# Z80_Card_for_Commodore_C64.net
KiCad netlist of a schematic drawn in Altium Designer
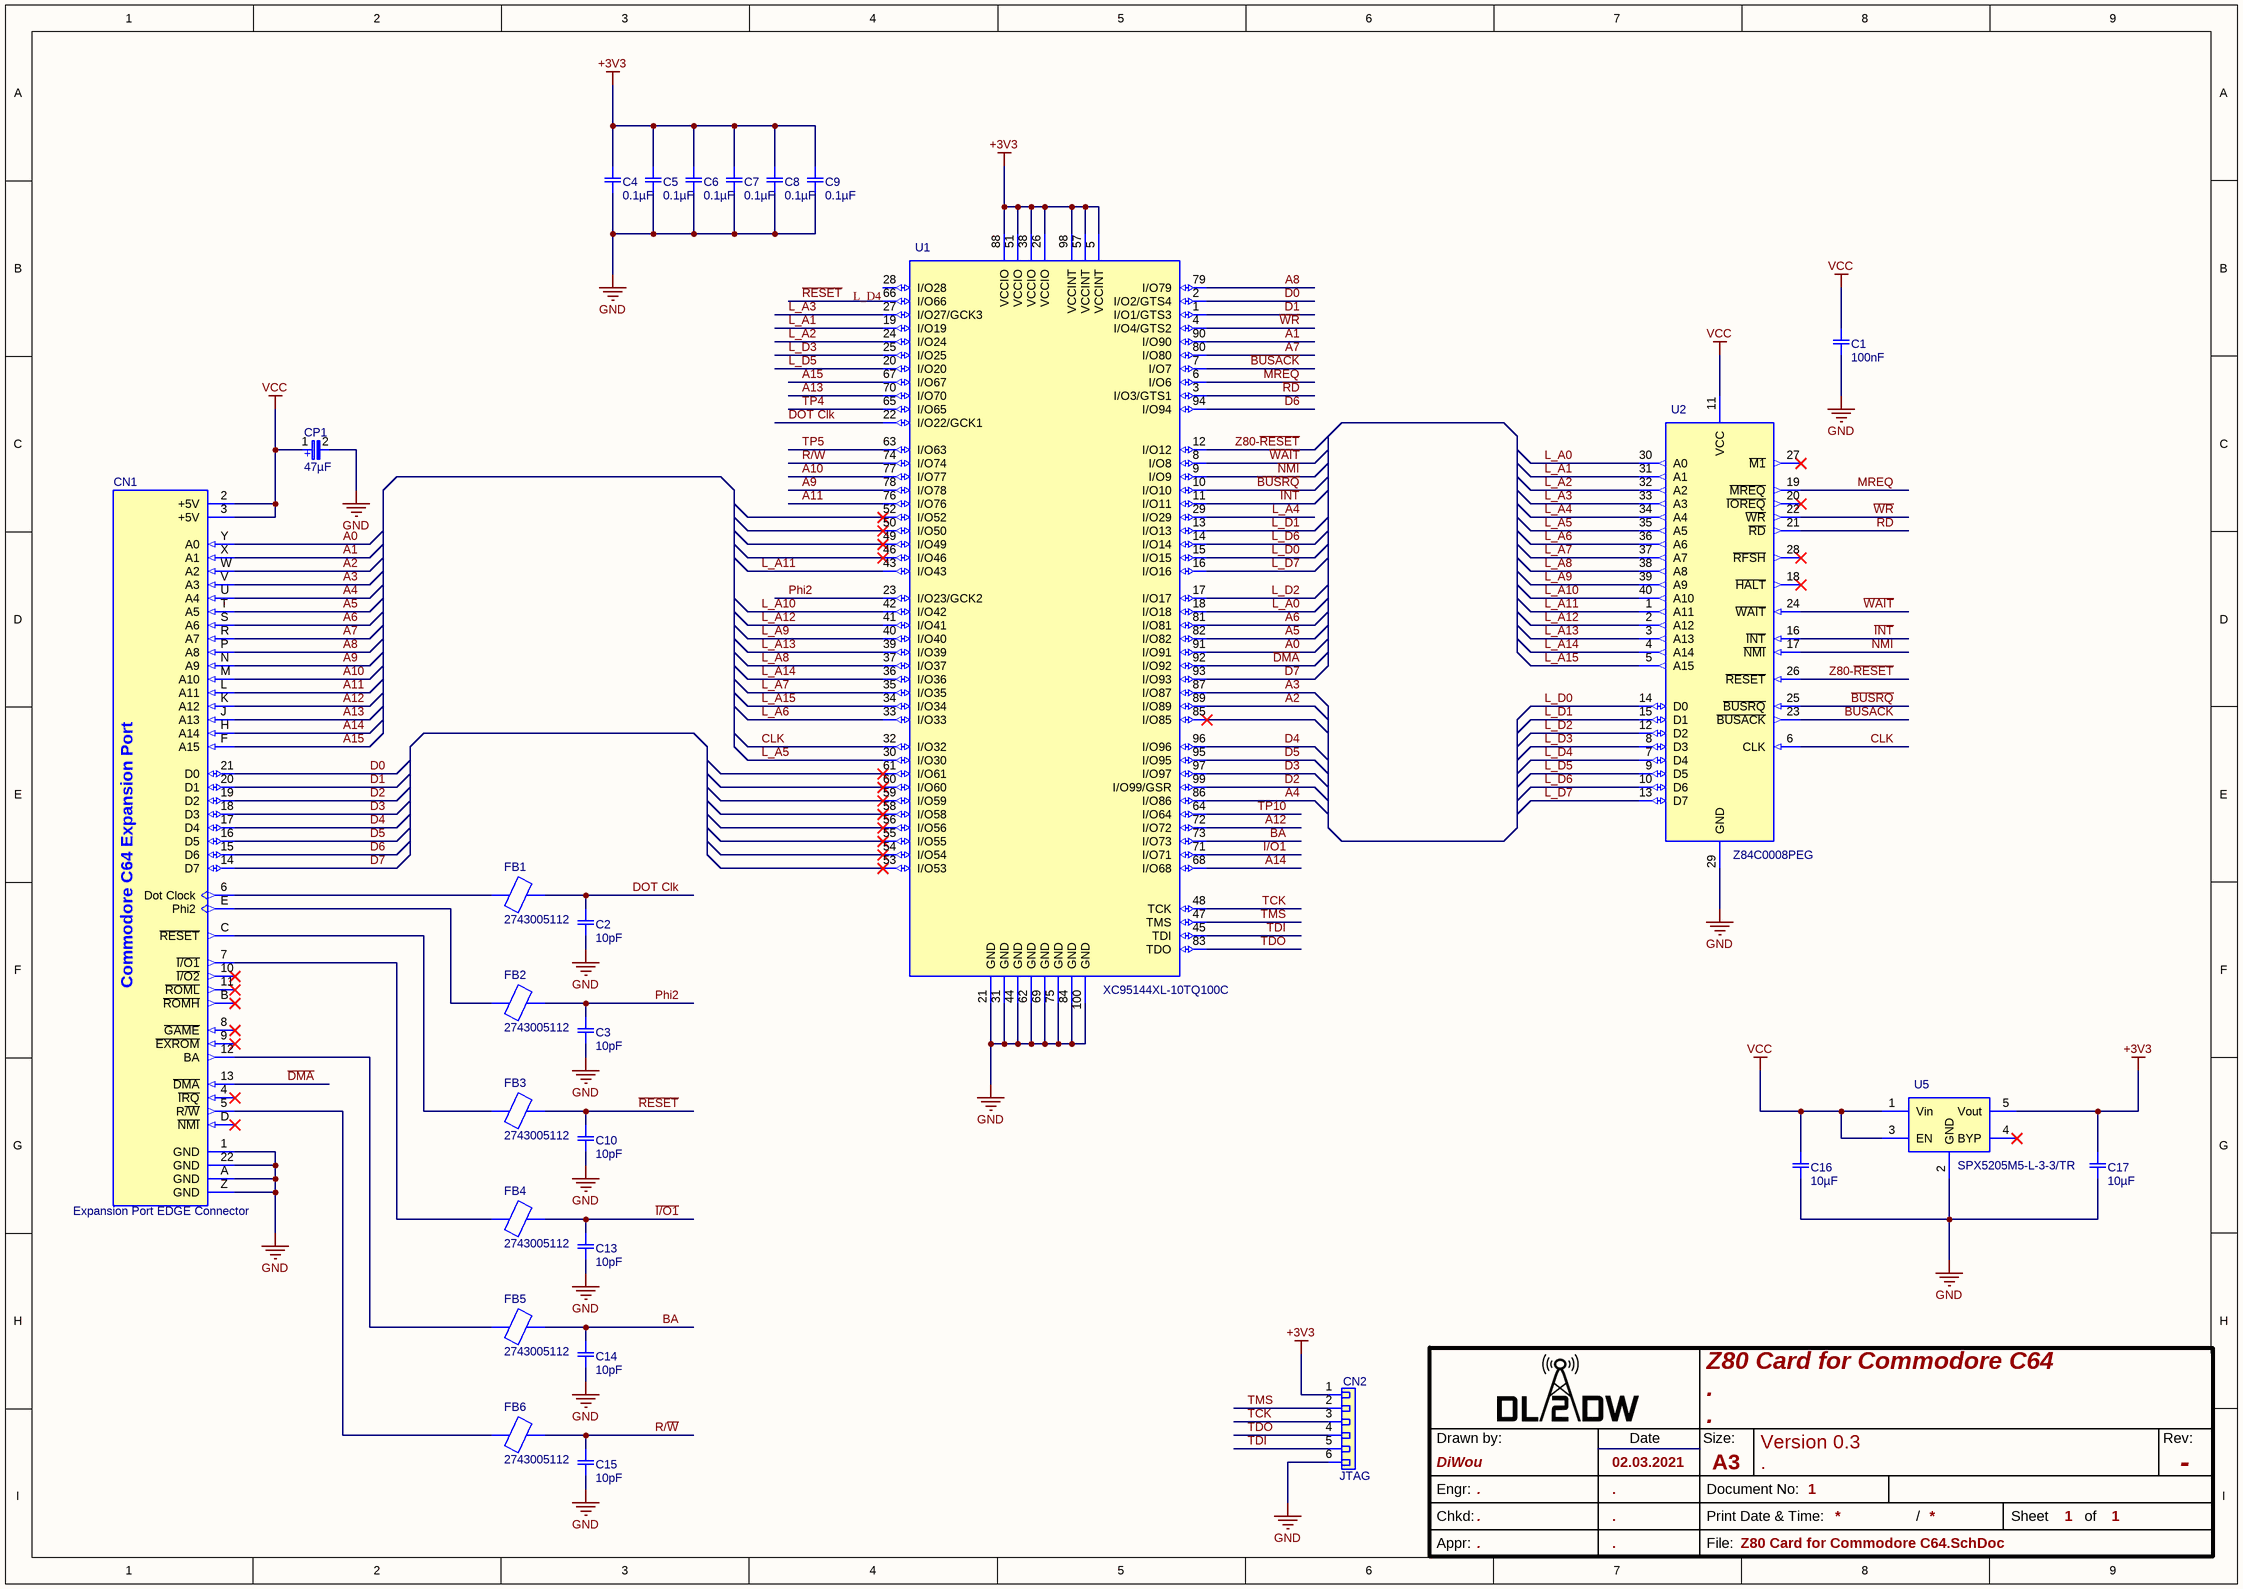
[diagram p0: Z80 Card for Commodore C64.SchDoc]

(export (version "E")
  (design (tool "Eeschema 10.0.6"))
  (components
    (comp (ref "C1")
      (value "100nF")
      (footprint "CAP Disc 100nF P2.54mm D5.5mm T3mm")
      (description "Ceramic Disc Capacitors 100nF -20%~+80% 50V Through Hole,P=2.54mm RoHS")
      (libsource (lib "PCB-Tech Cloud") (part "Capacitor"))
    )
    (comp (ref "C2")
      (value "10pF")
      (footprint "CAP CER 10PF 25V C0G-NP0 RADIAL Kemet C315C100J3G5TA")
      (description "CAP CER 10PF 25V C0G/NP0 RADIAL")
      (libsource (lib "PCB-Tech Cloud") (part "Capacitor"))
    )
    (comp (ref "C3")
      (value "10pF")
      (footprint "CAP CER 10PF 25V C0G-NP0 RADIAL Kemet C315C100J3G5TA")
      (description "CAP CER 10PF 25V C0G/NP0 RADIAL")
      (libsource (lib "PCB-Tech Cloud") (part "Capacitor"))
    )
    (comp (ref "C4")
      (value "0.1µF")
      (footprint "CAP 100nF SMD 0603 C0603C104J3RACTU")
      (fields (field (name "TOLERANCE") "5%") (field (name "VOLTAGE") "25V"))
      (libsource (lib "PCB-Tech Cloud") (part "Capacitor"))
    )
    (comp (ref "C5")
      (value "0.1µF")
      (footprint "CAP 100nF SMD 0603 C0603C104J3RACTU")
      (fields (field (name "TOLERANCE") "5%") (field (name "VOLTAGE") "25V"))
      (libsource (lib "PCB-Tech Cloud") (part "Capacitor"))
    )
    (comp (ref "C6")
      (value "0.1µF")
      (footprint "CAP 100nF SMD 0603 C0603C104J3RACTU")
      (fields (field (name "TOLERANCE") "5%") (field (name "VOLTAGE") "25V"))
      (libsource (lib "PCB-Tech Cloud") (part "Capacitor"))
    )
    (comp (ref "C7")
      (value "0.1µF")
      (footprint "CAP 100nF SMD 0603 C0603C104J3RACTU")
      (fields (field (name "TOLERANCE") "5%") (field (name "VOLTAGE") "25V"))
      (libsource (lib "PCB-Tech Cloud") (part "Capacitor"))
    )
    (comp (ref "C8")
      (value "0.1µF")
      (footprint "CAP 100nF SMD 0603 C0603C104J3RACTU")
      (fields (field (name "TOLERANCE") "5%") (field (name "VOLTAGE") "25V"))
      (libsource (lib "PCB-Tech Cloud") (part "Capacitor"))
    )
    (comp (ref "C9")
      (value "0.1µF")
      (footprint "CAP 100nF SMD 0603 C0603C104J3RACTU")
      (fields (field (name "TOLERANCE") "5%") (field (name "VOLTAGE") "25V"))
      (libsource (lib "PCB-Tech Cloud") (part "Capacitor"))
    )
    (comp (ref "C10")
      (value "10pF")
      (footprint "CAP CER 10PF 25V C0G-NP0 RADIAL Kemet C315C100J3G5TA")
      (description "CAP CER 10PF 25V C0G/NP0 RADIAL")
      (libsource (lib "PCB-Tech Cloud") (part "Capacitor"))
    )
    (comp (ref "C13")
      (value "10pF")
      (footprint "CAP CER 10PF 25V C0G-NP0 RADIAL Kemet C315C100J3G5TA")
      (description "CAP CER 10PF 25V C0G/NP0 RADIAL")
      (libsource (lib "PCB-Tech Cloud") (part "Capacitor"))
    )
    (comp (ref "C14")
      (value "10pF")
      (footprint "CAP CER 10PF 25V C0G-NP0 RADIAL Kemet C315C100J3G5TA")
      (description "CAP CER 10PF 25V C0G/NP0 RADIAL")
      (libsource (lib "PCB-Tech Cloud") (part "Capacitor"))
    )
    (comp (ref "C15")
      (value "10pF")
      (footprint "CAP CER 10PF 25V C0G-NP0 RADIAL Kemet C315C100J3G5TA")
      (description "CAP CER 10PF 25V C0G/NP0 RADIAL")
      (libsource (lib "PCB-Tech Cloud") (part "Capacitor"))
    )
    (comp (ref "C16")
      (value "10µF")
      (footprint "Kemet C0805CxxxK8RACTU Series H=1.4mm")
      (description "KEMET - C0805C106K8RACTU - CAP, 10µF, 10V, 10%, X7R, 0805")
      (fields (field (name "VOLTAGE") "10V") (field (name "TOLERANCE") "10%"))
      (libsource (lib "PCB-Tech Cloud") (part "Capacitor"))
    )
    (comp (ref "C17")
      (value "10µF")
      (footprint "Kemet C0805CxxxK8RACTU Series H=1.4mm")
      (description "KEMET - C0805C106K8RACTU - CAP, 10µF, 10V, 10%, X7R, 0805")
      (fields (field (name "VOLTAGE") "10V") (field (name "TOLERANCE") "10%"))
      (libsource (lib "PCB-Tech Cloud") (part "Capacitor"))
    )
    (comp (ref "CN1")
      (value "Expansion Port EDGE Connector")
      (footprint "C64 Expansion Port EDGE Connector")
      (description "Expansion Port EDGE Connector for Interface Cards")
      (libsource (lib "PCB-Tech Cloud") (part "C64 Expansion Port"))
    )
    (comp (ref "CN2")
      (value "JTAG")
      (footprint "Pin Header 01x06 2.54mm Horizontal Male")
      (description "CONN HEADER VERT 6POS 2.54MM")
      (libsource (lib "PCB-Tech Cloud") (part "CONN 01x06"))
    )
    (comp (ref "CP1")
      (value "47µF")
      (footprint "CAP 47µF16V D6mm H6.3mm P2.5mm")
      (description "Aluminum Electrolytic Capacitors - Leaded 47uF 105c")
      (fields (field (name "TOLERANCE") "20%"))
      (libsource (lib "PCB-Tech Cloud") (part "Polarized Capacitor"))
    )
    (comp (ref "FB1")
      (value "2743005112")
      (footprint "Ferrite Bead Fair Rite 2743005112")
      (description "Ferrite Beads Axial 91Ohm 100MHz T/R")
      (libsource (lib "PCB-Tech Cloud") (part "Ferrite Bead"))
    )
    (comp (ref "FB2")
      (value "2743005112")
      (footprint "Ferrite Bead Fair Rite 2743005112")
      (description "Ferrite Beads Axial 91Ohm 100MHz T/R")
      (libsource (lib "PCB-Tech Cloud") (part "Ferrite Bead"))
    )
    (comp (ref "FB3")
      (value "2743005112")
      (footprint "Ferrite Bead Fair Rite 2743005112")
      (description "Ferrite Beads Axial 91Ohm 100MHz T/R")
      (libsource (lib "PCB-Tech Cloud") (part "Ferrite Bead"))
    )
    (comp (ref "FB4")
      (value "2743005112")
      (footprint "Ferrite Bead Fair Rite 2743005112")
      (description "Ferrite Beads Axial 91Ohm 100MHz T/R")
      (libsource (lib "PCB-Tech Cloud") (part "Ferrite Bead"))
    )
    (comp (ref "FB5")
      (value "2743005112")
      (footprint "Ferrite Bead Fair Rite 2743005112")
      (description "Ferrite Beads Axial 91Ohm 100MHz T/R")
      (libsource (lib "PCB-Tech Cloud") (part "Ferrite Bead"))
    )
    (comp (ref "FB6")
      (value "2743005112")
      (footprint "Ferrite Bead Fair Rite 2743005112")
      (description "Ferrite Beads Axial 91Ohm 100MHz T/R")
      (libsource (lib "PCB-Tech Cloud") (part "Ferrite Bead"))
    )
    (comp (ref "U1")
      (value "XC95144XL-10TQ100C")
      (footprint "TQFP-100 P0.5mm XC95144XL-7TQ100C")
      (description "IC CPLD 144MC 7.5NS 100TQFP")
      (libsource (lib "PCB-Tech Cloud") (part "XC95144XL-TQG100C"))
    )
    (comp (ref "U2")
      (value "Z84C0008PEG")
      (footprint "Zilog Z80 CPU with Socket")
      (description "IC MPU Z80 8MHZ 40DIP")
      (fields (field (name "VOLTAGE") "5V"))
      (libsource (lib "PCB-Tech Cloud") (part "Zilog Z80 CPU"))
    )
    (comp (ref "U5")
      (value "SPX5205M5-L-3-3/TR")
      (footprint "SOT-23-5")
      (description "LDO Regulator Pos 3.3V 0.15A 5-Pin SOT-23 T/R")
      (libsource (lib "PCB-Tech Cloud") (part "SPX5205M5-L-3-3/TR"))
    )
  )
  (nets
    (net (code "1") (name "+3V3") (class "Default")
      (node (ref "C17") (pin "2") (pinfunction "2_2") (pintype "passive"))
      (node (ref "C4") (pin "2") (pinfunction "2_2") (pintype "passive"))
      (node (ref "C5") (pin "2") (pinfunction "2_2") (pintype "passive"))
      (node (ref "C6") (pin "2") (pinfunction "2_2") (pintype "passive"))
      (node (ref "C7") (pin "2") (pinfunction "2_2") (pintype "passive"))
      (node (ref "C8") (pin "2") (pinfunction "2_2") (pintype "passive"))
      (node (ref "C9") (pin "2") (pinfunction "2_2") (pintype "passive"))
      (node (ref "CN2") (pin "1") (pinfunction "1_1") (pintype "passive"))
      (node (ref "U1") (pin "26") (pinfunction "VCCIO_26") (pintype "power_in"))
      (node (ref "U1") (pin "38") (pinfunction "VCCIO_38") (pintype "power_in"))
      (node (ref "U1") (pin "5") (pinfunction "VCCINT_5") (pintype "power_in"))
      (node (ref "U1") (pin "51") (pinfunction "VCCIO_51") (pintype "power_in"))
      (node (ref "U1") (pin "57") (pinfunction "VCCINT_57") (pintype "power_in"))
      (node (ref "U1") (pin "88") (pinfunction "VCCIO_88") (pintype "power_in"))
      (node (ref "U1") (pin "98") (pinfunction "VCCINT_98") (pintype "power_in"))
      (node (ref "U5") (pin "5") (pinfunction "Vout_5") (pintype "power_in"))
    )
    (net (code "2") (name "/A0") (class "Default")
      (node (ref "CN1") (pin "Y") (pinfunction "A0_Y") (pintype "input"))
      (node (ref "U1") (pin "91") (pinfunction "I/O91_91") (pintype "bidirectional"))
    )
    (net (code "3") (name "/A1") (class "Default")
      (node (ref "CN1") (pin "X") (pinfunction "A1_X") (pintype "input"))
      (node (ref "U1") (pin "90") (pinfunction "I/O90_90") (pintype "bidirectional"))
    )
    (net (code "4") (name "/A2") (class "Default")
      (node (ref "CN1") (pin "W") (pinfunction "A2_W") (pintype "input"))
      (node (ref "U1") (pin "89") (pinfunction "I/O89_89") (pintype "bidirectional"))
    )
    (net (code "5") (name "/A3") (class "Default")
      (node (ref "CN1") (pin "V") (pinfunction "A3_V") (pintype "input"))
      (node (ref "U1") (pin "87") (pinfunction "I/O87_87") (pintype "bidirectional"))
    )
    (net (code "6") (name "/A4") (class "Default")
      (node (ref "CN1") (pin "U") (pinfunction "A4_U") (pintype "input"))
      (node (ref "U1") (pin "86") (pinfunction "I/O86_86") (pintype "bidirectional"))
    )
    (net (code "7") (name "/A5") (class "Default")
      (node (ref "CN1") (pin "T") (pinfunction "A5_T") (pintype "input"))
      (node (ref "U1") (pin "82") (pinfunction "I/O82_82") (pintype "bidirectional"))
    )
    (net (code "8") (name "/A6") (class "Default")
      (node (ref "CN1") (pin "S") (pinfunction "A6_S") (pintype "input"))
      (node (ref "U1") (pin "81") (pinfunction "I/O81_81") (pintype "bidirectional"))
    )
    (net (code "9") (name "/A7") (class "Default")
      (node (ref "CN1") (pin "R") (pinfunction "A7_R") (pintype "input"))
      (node (ref "U1") (pin "80") (pinfunction "I/O80_80") (pintype "bidirectional"))
    )
    (net (code "10") (name "/A8") (class "Default")
      (node (ref "CN1") (pin "P") (pinfunction "A8_P") (pintype "input"))
      (node (ref "U1") (pin "79") (pinfunction "I/O79_79") (pintype "bidirectional"))
    )
    (net (code "11") (name "/A9") (class "Default")
      (node (ref "CN1") (pin "N") (pinfunction "A9_N") (pintype "input"))
      (node (ref "U1") (pin "78") (pinfunction "I/O78_78") (pintype "bidirectional"))
    )
    (net (code "12") (name "/A10") (class "Default")
      (node (ref "CN1") (pin "M") (pinfunction "A10_M") (pintype "input"))
      (node (ref "U1") (pin "77") (pinfunction "I/O77_77") (pintype "bidirectional"))
    )
    (net (code "13") (name "/A11") (class "Default")
      (node (ref "CN1") (pin "L") (pinfunction "A11_L") (pintype "input"))
      (node (ref "U1") (pin "76") (pinfunction "I/O76_76") (pintype "bidirectional"))
    )
    (net (code "14") (name "/A12") (class "Default")
      (node (ref "CN1") (pin "K") (pinfunction "A12_K") (pintype "input"))
      (node (ref "U1") (pin "72") (pinfunction "I/O72_72") (pintype "bidirectional"))
    )
    (net (code "15") (name "/A13") (class "Default")
      (node (ref "CN1") (pin "J") (pinfunction "A13_J") (pintype "input"))
      (node (ref "U1") (pin "70") (pinfunction "I/O70_70") (pintype "bidirectional"))
    )
    (net (code "16") (name "/A14") (class "Default")
      (node (ref "CN1") (pin "H") (pinfunction "A14_H") (pintype "input"))
      (node (ref "U1") (pin "68") (pinfunction "I/O68_68") (pintype "bidirectional"))
    )
    (net (code "17") (name "/A15") (class "Default")
      (node (ref "CN1") (pin "F") (pinfunction "A15_F") (pintype "input"))
      (node (ref "U1") (pin "67") (pinfunction "I/O67_67") (pintype "bidirectional"))
    )
    (net (code "18") (name "/BA") (class "Default")
      (node (ref "C14") (pin "2") (pinfunction "2_2") (pintype "passive"))
      (node (ref "FB5") (pin "2") (pinfunction "2_2") (pintype "passive"))
      (node (ref "U1") (pin "73") (pinfunction "I/O73_73") (pintype "bidirectional"))
    )
    (net (code "19") (name "/CLK") (class "Default")
      (node (ref "U1") (pin "32") (pinfunction "I/O32_32") (pintype "bidirectional"))
      (node (ref "U2") (pin "6") (pinfunction "CLK_6") (pintype "input"))
    )
    (net (code "20") (name "/D0") (class "Default")
      (node (ref "CN1") (pin "21") (pinfunction "D0_21") (pintype "bidirectional"))
      (node (ref "U1") (pin "2") (pinfunction "I/O2/GTS4_2") (pintype "bidirectional"))
    )
    (net (code "21") (name "/D1") (class "Default")
      (node (ref "CN1") (pin "20") (pinfunction "D1_20") (pintype "bidirectional"))
      (node (ref "U1") (pin "1") (pinfunction "I/O1/GTS3_1") (pintype "bidirectional"))
    )
    (net (code "22") (name "/D2") (class "Default")
      (node (ref "CN1") (pin "19") (pinfunction "D2_19") (pintype "bidirectional"))
      (node (ref "U1") (pin "99") (pinfunction "I/O99/GSR_99") (pintype "bidirectional"))
    )
    (net (code "23") (name "/D3") (class "Default")
      (node (ref "CN1") (pin "18") (pinfunction "D3_18") (pintype "bidirectional"))
      (node (ref "U1") (pin "97") (pinfunction "I/O97_97") (pintype "bidirectional"))
    )
    (net (code "24") (name "/D4") (class "Default")
      (node (ref "CN1") (pin "17") (pinfunction "D4_17") (pintype "bidirectional"))
      (node (ref "U1") (pin "96") (pinfunction "I/O96_96") (pintype "bidirectional"))
    )
    (net (code "25") (name "/D5") (class "Default")
      (node (ref "CN1") (pin "16") (pinfunction "D5_16") (pintype "bidirectional"))
      (node (ref "U1") (pin "95") (pinfunction "I/O95_95") (pintype "bidirectional"))
    )
    (net (code "26") (name "/D6") (class "Default")
      (node (ref "CN1") (pin "15") (pinfunction "D6_15") (pintype "bidirectional"))
      (node (ref "U1") (pin "94") (pinfunction "I/O94_94") (pintype "bidirectional"))
    )
    (net (code "27") (name "/D7") (class "Default")
      (node (ref "CN1") (pin "14") (pinfunction "D7_14") (pintype "bidirectional"))
      (node (ref "U1") (pin "93") (pinfunction "I/O93_93") (pintype "bidirectional"))
    )
    (net (code "28") (name "/DOT Clk") (class "Default")
      (node (ref "C2") (pin "2") (pinfunction "2_2") (pintype "passive"))
      (node (ref "FB1") (pin "2") (pinfunction "2_2") (pintype "passive"))
      (node (ref "U1") (pin "22") (pinfunction "I/O22/GCK1_22") (pintype "bidirectional"))
    )
    (net (code "29") (name "/L_A0") (class "Default")
      (node (ref "U1") (pin "18") (pinfunction "I/O18_18") (pintype "bidirectional"))
      (node (ref "U2") (pin "30") (pinfunction "A0_30") (pintype "output"))
    )
    (net (code "30") (name "/L_A1") (class "Default")
      (node (ref "U1") (pin "19") (pinfunction "I/O19_19") (pintype "bidirectional"))
      (node (ref "U2") (pin "31") (pinfunction "A1_31") (pintype "output"))
    )
    (net (code "31") (name "/L_A2") (class "Default")
      (node (ref "U1") (pin "24") (pinfunction "I/O24_24") (pintype "bidirectional"))
      (node (ref "U2") (pin "32") (pinfunction "A2_32") (pintype "output"))
    )
    (net (code "32") (name "/L_A3") (class "Default")
      (node (ref "U1") (pin "27") (pinfunction "I/O27/GCK3_27") (pintype "bidirectional"))
      (node (ref "U2") (pin "33") (pinfunction "A3_33") (pintype "output"))
    )
    (net (code "33") (name "/L_A4") (class "Default")
      (node (ref "U1") (pin "29") (pinfunction "I/O29_29") (pintype "bidirectional"))
      (node (ref "U2") (pin "34") (pinfunction "A4_34") (pintype "output"))
    )
    (net (code "34") (name "/L_A5") (class "Default")
      (node (ref "U1") (pin "30") (pinfunction "I/O30_30") (pintype "bidirectional"))
      (node (ref "U2") (pin "35") (pinfunction "A5_35") (pintype "output"))
    )
    (net (code "35") (name "/L_A6") (class "Default")
      (node (ref "U1") (pin "33") (pinfunction "I/O33_33") (pintype "bidirectional"))
      (node (ref "U2") (pin "36") (pinfunction "A6_36") (pintype "output"))
    )
    (net (code "36") (name "/L_A7") (class "Default")
      (node (ref "U1") (pin "35") (pinfunction "I/O35_35") (pintype "bidirectional"))
      (node (ref "U2") (pin "37") (pinfunction "A7_37") (pintype "output"))
    )
    (net (code "37") (name "/L_A8") (class "Default")
      (node (ref "U1") (pin "37") (pinfunction "I/O37_37") (pintype "bidirectional"))
      (node (ref "U2") (pin "38") (pinfunction "A8_38") (pintype "output"))
    )
    (net (code "38") (name "/L_A9") (class "Default")
      (node (ref "U1") (pin "40") (pinfunction "I/O40_40") (pintype "bidirectional"))
      (node (ref "U2") (pin "39") (pinfunction "A9_39") (pintype "output"))
    )
    (net (code "39") (name "/L_A10") (class "Default")
      (node (ref "U1") (pin "42") (pinfunction "I/O42_42") (pintype "bidirectional"))
      (node (ref "U2") (pin "40") (pinfunction "A10_40") (pintype "output"))
    )
    (net (code "40") (name "/L_A11") (class "Default")
      (node (ref "U1") (pin "43") (pinfunction "I/O43_43") (pintype "bidirectional"))
      (node (ref "U2") (pin "1") (pinfunction "A11_1") (pintype "output"))
    )
    (net (code "41") (name "/L_A12") (class "Default")
      (node (ref "U1") (pin "41") (pinfunction "I/O41_41") (pintype "bidirectional"))
      (node (ref "U2") (pin "2") (pinfunction "A12_2") (pintype "output"))
    )
    (net (code "42") (name "/L_A13") (class "Default")
      (node (ref "U1") (pin "39") (pinfunction "I/O39_39") (pintype "bidirectional"))
      (node (ref "U2") (pin "3") (pinfunction "A13_3") (pintype "output"))
    )
    (net (code "43") (name "/L_A14") (class "Default")
      (node (ref "U1") (pin "36") (pinfunction "I/O36_36") (pintype "bidirectional"))
      (node (ref "U2") (pin "4") (pinfunction "A14_4") (pintype "output"))
    )
    (net (code "44") (name "/L_A15") (class "Default")
      (node (ref "U1") (pin "34") (pinfunction "I/O34_34") (pintype "bidirectional"))
      (node (ref "U2") (pin "5") (pinfunction "A15_5") (pintype "output"))
    )
    (net (code "45") (name "/L_D0") (class "Default")
      (node (ref "U1") (pin "15") (pinfunction "I/O15_15") (pintype "bidirectional"))
      (node (ref "U2") (pin "14") (pinfunction "D0_14") (pintype "bidirectional"))
    )
    (net (code "46") (name "/L_D1") (class "Default")
      (node (ref "U1") (pin "13") (pinfunction "I/O13_13") (pintype "bidirectional"))
      (node (ref "U2") (pin "15") (pinfunction "D1_15") (pintype "bidirectional"))
    )
    (net (code "47") (name "/L_D2") (class "Default")
      (node (ref "U1") (pin "17") (pinfunction "I/O17_17") (pintype "bidirectional"))
      (node (ref "U2") (pin "12") (pinfunction "D2_12") (pintype "bidirectional"))
    )
    (net (code "48") (name "/L_D3") (class "Default")
      (node (ref "U1") (pin "25") (pinfunction "I/O25_25") (pintype "bidirectional"))
      (node (ref "U2") (pin "8") (pinfunction "D3_8") (pintype "bidirectional"))
    )
    (net (code "49") (name "/L_D4") (class "Default")
      (node (ref "U1") (pin "28") (pinfunction "I/O28_28") (pintype "bidirectional"))
      (node (ref "U2") (pin "7") (pinfunction "D4_7") (pintype "bidirectional"))
    )
    (net (code "50") (name "/L_D5") (class "Default")
      (node (ref "U1") (pin "20") (pinfunction "I/O20_20") (pintype "bidirectional"))
      (node (ref "U2") (pin "9") (pinfunction "D5_9") (pintype "bidirectional"))
    )
    (net (code "51") (name "/L_D6") (class "Default")
      (node (ref "U1") (pin "14") (pinfunction "I/O14_14") (pintype "bidirectional"))
      (node (ref "U2") (pin "10") (pinfunction "D6_10") (pintype "bidirectional"))
    )
    (net (code "52") (name "/L_D7") (class "Default")
      (node (ref "U1") (pin "16") (pinfunction "I/O16_16") (pintype "bidirectional"))
      (node (ref "U2") (pin "13") (pinfunction "D7_13") (pintype "bidirectional"))
    )
    (net (code "53") (name "/MREQ") (class "Default")
      (node (ref "U1") (pin "6") (pinfunction "I/O6_6") (pintype "bidirectional"))
      (node (ref "U2") (pin "19") (pinfunction "~{MREQ}_19") (pintype "output"))
    )
    (net (code "54") (name "/Phi2") (class "Default")
      (node (ref "C3") (pin "2") (pinfunction "2_2") (pintype "passive"))
      (node (ref "FB2") (pin "2") (pinfunction "2_2") (pintype "passive"))
      (node (ref "U1") (pin "23") (pinfunction "I/O23/GCK2_23") (pintype "bidirectional"))
    )
    (net (code "55") (name "/R{slash}~{W}") (class "Default")
      (node (ref "C15") (pin "2") (pinfunction "2_2") (pintype "passive"))
      (node (ref "FB6") (pin "2") (pinfunction "2_2") (pintype "passive"))
      (node (ref "U1") (pin "74") (pinfunction "I/O74_74") (pintype "bidirectional"))
    )
    (net (code "56") (name "/TCK") (class "Default")
      (node (ref "CN2") (pin "3") (pinfunction "3_3") (pintype "passive"))
      (node (ref "U1") (pin "48") (pinfunction "TCK_48") (pintype "bidirectional"))
    )
    (net (code "57") (name "/TDI") (class "Default")
      (node (ref "CN2") (pin "5") (pinfunction "5_5") (pintype "passive"))
      (node (ref "U1") (pin "45") (pinfunction "TDI_45") (pintype "bidirectional"))
    )
    (net (code "58") (name "/TDO") (class "Default")
      (node (ref "CN2") (pin "4") (pinfunction "4_4") (pintype "passive"))
      (node (ref "U1") (pin "83") (pinfunction "TDO_83") (pintype "bidirectional"))
    )
    (net (code "59") (name "/TMS") (class "Default")
      (node (ref "CN2") (pin "2") (pinfunction "2_2") (pintype "passive"))
      (node (ref "U1") (pin "47") (pinfunction "TMS_47") (pintype "bidirectional"))
    )
    (net (code "60") (name "/TP4") (class "Default")
      (node (ref "U1") (pin "65") (pinfunction "I/O65_65") (pintype "bidirectional"))
    )
    (net (code "61") (name "/TP5") (class "Default")
      (node (ref "U1") (pin "63") (pinfunction "I/O63_63") (pintype "bidirectional"))
    )
    (net (code "62") (name "/TP10") (class "Default")
      (node (ref "U1") (pin "64") (pinfunction "I/O64_64") (pintype "bidirectional"))
    )
    (net (code "63") (name "/Z80-~{RESET}") (class "Default")
      (node (ref "U1") (pin "12") (pinfunction "I/O12_12") (pintype "bidirectional"))
      (node (ref "U2") (pin "26") (pinfunction "~{RESET}_26") (pintype "input"))
    )
    (net (code "64") (name "/~{BUSACK}") (class "Default")
      (node (ref "U1") (pin "7") (pinfunction "I/O7_7") (pintype "bidirectional"))
      (node (ref "U2") (pin "23") (pinfunction "~{BUSACK}_23") (pintype "output"))
    )
    (net (code "65") (name "/~{BUSRQ}") (class "Default")
      (node (ref "U1") (pin "10") (pinfunction "I/O10_10") (pintype "bidirectional"))
      (node (ref "U2") (pin "25") (pinfunction "~{BUSRQ}_25") (pintype "input"))
    )
    (net (code "66") (name "/~{DMA}") (class "Default")
      (node (ref "CN1") (pin "13") (pinfunction "~{DMA}_13") (pintype "input"))
      (node (ref "U1") (pin "92") (pinfunction "I/O92_92") (pintype "bidirectional"))
    )
    (net (code "67") (name "/~{INT}") (class "Default")
      (node (ref "U1") (pin "11") (pinfunction "I/O11_11") (pintype "bidirectional"))
      (node (ref "U2") (pin "16") (pinfunction "~{INT}_16") (pintype "input"))
    )
    (net (code "68") (name "/~{I{slash}O1}") (class "Default")
      (node (ref "C13") (pin "2") (pinfunction "2_2") (pintype "passive"))
      (node (ref "FB4") (pin "2") (pinfunction "2_2") (pintype "passive"))
      (node (ref "U1") (pin "71") (pinfunction "I/O71_71") (pintype "bidirectional"))
    )
    (net (code "69") (name "/~{NMI}") (class "Default")
      (node (ref "U1") (pin "9") (pinfunction "I/O9_9") (pintype "bidirectional"))
      (node (ref "U2") (pin "17") (pinfunction "~{NMI}_17") (pintype "input"))
    )
    (net (code "70") (name "/~{RD}") (class "Default")
      (node (ref "U1") (pin "3") (pinfunction "I/O3/GTS1_3") (pintype "bidirectional"))
      (node (ref "U2") (pin "21") (pinfunction "~{RD}_21") (pintype "output"))
    )
    (net (code "71") (name "/~{RESET}") (class "Default")
      (node (ref "C10") (pin "2") (pinfunction "2_2") (pintype "passive"))
      (node (ref "FB3") (pin "2") (pinfunction "2_2") (pintype "passive"))
      (node (ref "U1") (pin "66") (pinfunction "I/O66_66") (pintype "bidirectional"))
    )
    (net (code "72") (name "/~{WAIT}") (class "Default")
      (node (ref "U1") (pin "8") (pinfunction "I/O8_8") (pintype "bidirectional"))
      (node (ref "U2") (pin "24") (pinfunction "~{WAIT}_24") (pintype "input"))
    )
    (net (code "73") (name "/~{WR}") (class "Default")
      (node (ref "U1") (pin "4") (pinfunction "I/O4/GTS2_4") (pintype "bidirectional"))
      (node (ref "U2") (pin "22") (pinfunction "~{WR}_22") (pintype "output"))
    )
    (net (code "74") (name "GND") (class "Default")
      (node (ref "C1") (pin "1") (pinfunction "1_1") (pintype "passive"))
      (node (ref "C10") (pin "1") (pinfunction "1_1") (pintype "passive"))
      (node (ref "C13") (pin "1") (pinfunction "1_1") (pintype "passive"))
      (node (ref "C14") (pin "1") (pinfunction "1_1") (pintype "passive"))
      (node (ref "C15") (pin "1") (pinfunction "1_1") (pintype "passive"))
      (node (ref "C16") (pin "1") (pinfunction "1_1") (pintype "passive"))
      (node (ref "C17") (pin "1") (pinfunction "1_1") (pintype "passive"))
      (node (ref "C2") (pin "1") (pinfunction "1_1") (pintype "passive"))
      (node (ref "C3") (pin "1") (pinfunction "1_1") (pintype "passive"))
      (node (ref "C4") (pin "1") (pinfunction "1_1") (pintype "passive"))
      (node (ref "C5") (pin "1") (pinfunction "1_1") (pintype "passive"))
      (node (ref "C6") (pin "1") (pinfunction "1_1") (pintype "passive"))
      (node (ref "C7") (pin "1") (pinfunction "1_1") (pintype "passive"))
      (node (ref "C8") (pin "1") (pinfunction "1_1") (pintype "passive"))
      (node (ref "C9") (pin "1") (pinfunction "1_1") (pintype "passive"))
      (node (ref "CN1") (pin "1") (pinfunction "GND_1") (pintype "power_in"))
      (node (ref "CN1") (pin "22") (pinfunction "GND_22") (pintype "power_in"))
      (node (ref "CN1") (pin "A") (pinfunction "GND_A") (pintype "power_in"))
      (node (ref "CN1") (pin "Z") (pinfunction "GND_Z") (pintype "power_in"))
      (node (ref "CN2") (pin "6") (pinfunction "6_6") (pintype "passive"))
      (node (ref "CP1") (pin "2") (pinfunction "2_2") (pintype "passive"))
      (node (ref "U1") (pin "100") (pinfunction "GND_100") (pintype "passive"))
      (node (ref "U1") (pin "21") (pinfunction "GND_21") (pintype "passive"))
      (node (ref "U1") (pin "31") (pinfunction "GND_31") (pintype "passive"))
      (node (ref "U1") (pin "44") (pinfunction "GND_44") (pintype "passive"))
      (node (ref "U1") (pin "62") (pinfunction "GND_62") (pintype "passive"))
      (node (ref "U1") (pin "69") (pinfunction "GND_69") (pintype "passive"))
      (node (ref "U1") (pin "75") (pinfunction "GND_75") (pintype "passive"))
      (node (ref "U1") (pin "84") (pinfunction "GND_84") (pintype "passive"))
      (node (ref "U2") (pin "29") (pinfunction "GND_29") (pintype "power_in"))
      (node (ref "U5") (pin "2") (pinfunction "GND_2") (pintype "power_in"))
    )
    (net (code "75") (name "Net-(CN1-BA)") (class "Default")
      (node (ref "CN1") (pin "12") (pinfunction "BA_12") (pintype "output"))
      (node (ref "FB5") (pin "1") (pinfunction "1_1") (pintype "passive"))
    )
    (net (code "76") (name "Net-(CN1-Dot_Clock)") (class "Default")
      (node (ref "CN1") (pin "6") (pinfunction "Dot_Clock_6") (pintype "output"))
      (node (ref "FB1") (pin "1") (pinfunction "1_1") (pintype "passive"))
    )
    (net (code "77") (name "Net-(CN1-Phi2)") (class "Default")
      (node (ref "CN1") (pin "E") (pinfunction "Phi2_E") (pintype "output"))
      (node (ref "FB2") (pin "1") (pinfunction "1_1") (pintype "passive"))
    )
    (net (code "78") (name "Net-(CN1-R~{{slash}W})") (class "Default")
      (node (ref "CN1") (pin "5") (pinfunction "R~{/W}_5") (pintype "output"))
      (node (ref "FB6") (pin "1") (pinfunction "1_1") (pintype "passive"))
    )
    (net (code "79") (name "Net-(CN1-~{I{slash}O1})") (class "Default")
      (node (ref "CN1") (pin "7") (pinfunction "~{I/O1}_7") (pintype "output"))
      (node (ref "FB4") (pin "1") (pinfunction "1_1") (pintype "passive"))
    )
    (net (code "80") (name "Net-(CN1-~{RESET})") (class "Default")
      (node (ref "CN1") (pin "C") (pinfunction "~{RESET}_C") (pintype "output"))
      (node (ref "FB3") (pin "1") (pinfunction "1_1") (pintype "passive"))
    )
    (net (code "81") (name "VCC") (class "Default")
      (node (ref "C1") (pin "2") (pinfunction "2_2") (pintype "passive"))
      (node (ref "C16") (pin "2") (pinfunction "2_2") (pintype "passive"))
      (node (ref "CN1") (pin "2") (pinfunction "+5V_2") (pintype "power_in"))
      (node (ref "CN1") (pin "3") (pinfunction "+5V_3") (pintype "power_in"))
      (node (ref "CP1") (pin "1") (pinfunction "1_1") (pintype "passive"))
      (node (ref "U2") (pin "11") (pinfunction "VCC_11") (pintype "power_in"))
      (node (ref "U5") (pin "1") (pinfunction "Vin_1") (pintype "power_in"))
      (node (ref "U5") (pin "3") (pinfunction "EN_3") (pintype "passive"))
    )
    (net (code "82") (name "unconnected-(CN1-~{EXROM}-Pad9)") (class "Default")
      (node (ref "CN1") (pin "9") (pinfunction "~{EXROM}_9") (pintype "input+no_connect"))
    )
    (net (code "83") (name "unconnected-(CN1-~{GAME}-Pad8)") (class "Default")
      (node (ref "CN1") (pin "8") (pinfunction "~{GAME}_8") (pintype "input+no_connect"))
    )
    (net (code "84") (name "unconnected-(CN1-~{IRQ}-Pad4)") (class "Default")
      (node (ref "CN1") (pin "4") (pinfunction "~{IRQ}_4") (pintype "input+no_connect"))
    )
    (net (code "85") (name "unconnected-(CN1-~{I{slash}O2}-Pad10)") (class "Default")
      (node (ref "CN1") (pin "10") (pinfunction "~{I/O2}_10") (pintype "output+no_connect"))
    )
    (net (code "86") (name "unconnected-(CN1-~{NMI}-PadD)") (class "Default")
      (node (ref "CN1") (pin "D") (pinfunction "~{NMI}_D") (pintype "input+no_connect"))
    )
    (net (code "87") (name "unconnected-(CN1-~{ROMH}-PadB)") (class "Default")
      (node (ref "CN1") (pin "B") (pinfunction "~{ROMH}_B") (pintype "output+no_connect"))
    )
    (net (code "88") (name "unconnected-(CN1-~{ROML}-Pad11)") (class "Default")
      (node (ref "CN1") (pin "11") (pinfunction "~{ROML}_11") (pintype "output+no_connect"))
    )
    (net (code "89") (name "unconnected-(U1-I{slash}O46-Pad46)") (class "Default")
      (node (ref "U1") (pin "46") (pinfunction "I/O46_46") (pintype "bidirectional+no_connect"))
    )
    (net (code "90") (name "unconnected-(U1-I{slash}O49-Pad49)") (class "Default")
      (node (ref "U1") (pin "49") (pinfunction "I/O49_49") (pintype "bidirectional+no_connect"))
    )
    (net (code "91") (name "unconnected-(U1-I{slash}O50-Pad50)") (class "Default")
      (node (ref "U1") (pin "50") (pinfunction "I/O50_50") (pintype "bidirectional+no_connect"))
    )
    (net (code "92") (name "unconnected-(U1-I{slash}O52-Pad52)") (class "Default")
      (node (ref "U1") (pin "52") (pinfunction "I/O52_52") (pintype "bidirectional+no_connect"))
    )
    (net (code "93") (name "unconnected-(U1-I{slash}O53-Pad53)") (class "Default")
      (node (ref "U1") (pin "53") (pinfunction "I/O53_53") (pintype "bidirectional+no_connect"))
    )
    (net (code "94") (name "unconnected-(U1-I{slash}O54-Pad54)") (class "Default")
      (node (ref "U1") (pin "54") (pinfunction "I/O54_54") (pintype "bidirectional+no_connect"))
    )
    (net (code "95") (name "unconnected-(U1-I{slash}O55-Pad55)") (class "Default")
      (node (ref "U1") (pin "55") (pinfunction "I/O55_55") (pintype "bidirectional+no_connect"))
    )
    (net (code "96") (name "unconnected-(U1-I{slash}O56-Pad56)") (class "Default")
      (node (ref "U1") (pin "56") (pinfunction "I/O56_56") (pintype "bidirectional+no_connect"))
    )
    (net (code "97") (name "unconnected-(U1-I{slash}O58-Pad58)") (class "Default")
      (node (ref "U1") (pin "58") (pinfunction "I/O58_58") (pintype "bidirectional+no_connect"))
    )
    (net (code "98") (name "unconnected-(U1-I{slash}O59-Pad59)") (class "Default")
      (node (ref "U1") (pin "59") (pinfunction "I/O59_59") (pintype "bidirectional+no_connect"))
    )
    (net (code "99") (name "unconnected-(U1-I{slash}O60-Pad60)") (class "Default")
      (node (ref "U1") (pin "60") (pinfunction "I/O60_60") (pintype "bidirectional+no_connect"))
    )
    (net (code "100") (name "unconnected-(U1-I{slash}O61-Pad61)") (class "Default")
      (node (ref "U1") (pin "61") (pinfunction "I/O61_61") (pintype "bidirectional+no_connect"))
    )
    (net (code "101") (name "unconnected-(U1-I{slash}O85-Pad85)") (class "Default")
      (node (ref "U1") (pin "85") (pinfunction "I/O85_85") (pintype "bidirectional+no_connect"))
    )
    (net (code "102") (name "unconnected-(U2-~{HALT}-Pad18)") (class "Default")
      (node (ref "U2") (pin "18") (pinfunction "~{HALT}_18") (pintype "output+no_connect"))
    )
    (net (code "103") (name "unconnected-(U2-~{IOREQ}-Pad20)") (class "Default")
      (node (ref "U2") (pin "20") (pinfunction "~{IOREQ}_20") (pintype "output+no_connect"))
    )
    (net (code "104") (name "unconnected-(U2-~{M1}-Pad27)") (class "Default")
      (node (ref "U2") (pin "27") (pinfunction "~{M1}_27") (pintype "output+no_connect"))
    )
    (net (code "105") (name "unconnected-(U2-~{RFSH}-Pad28)") (class "Default")
      (node (ref "U2") (pin "28") (pinfunction "~{RFSH}_28") (pintype "output+no_connect"))
    )
    (net (code "106") (name "unconnected-(U5-BYP-Pad4)") (class "Default")
      (node (ref "U5") (pin "4") (pinfunction "BYP_4") (pintype "passive+no_connect"))
    )
  )
)
